# ShrewSpecs-1-2.net
KiCad netlist of a schematic drawn in EAGLE
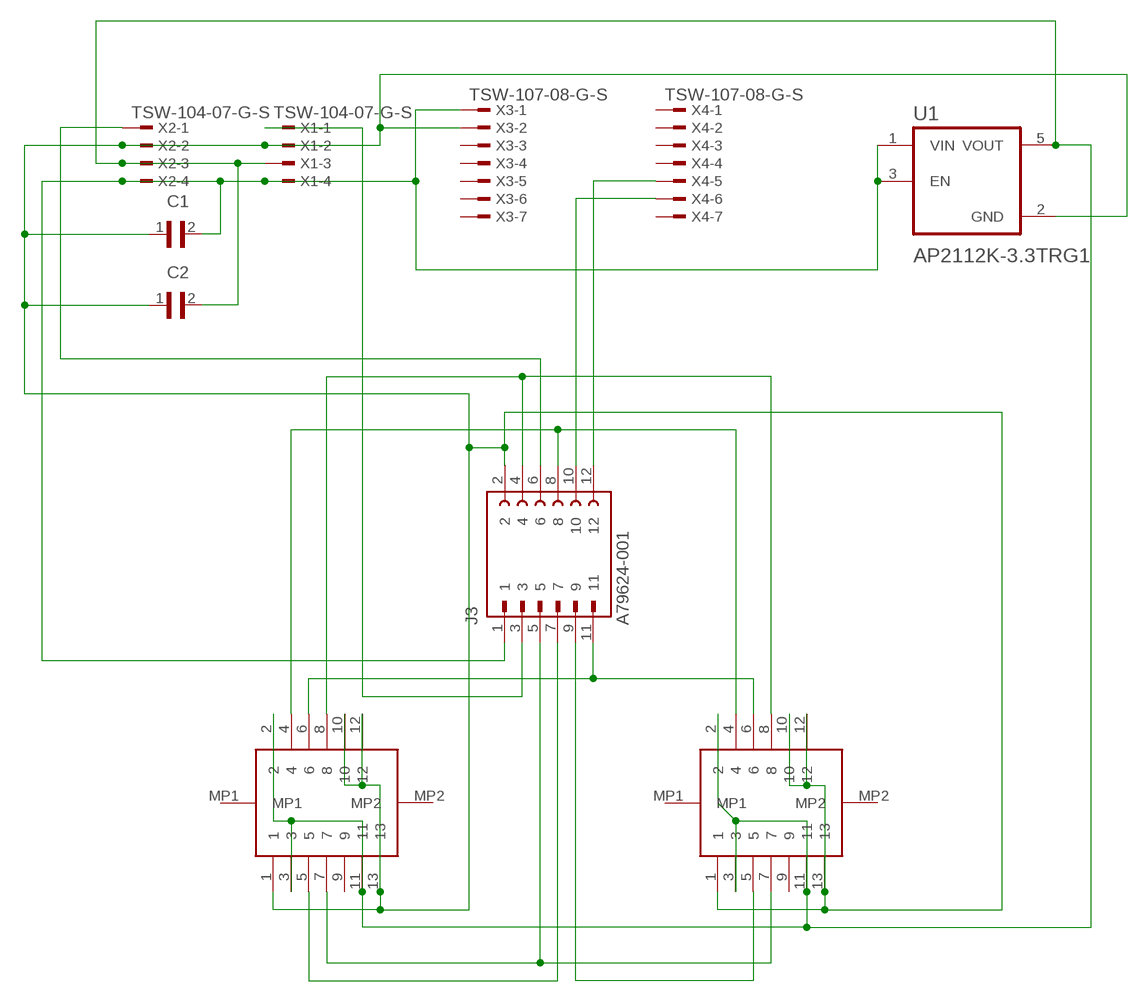
[diagram p0: schematic, sheet 1]

(export (version "E")
  (design (tool "Eeschema 10.0.6"))
  (components
    (comp (ref "C1")
      (value "CL21A106KOQNNNE")
      (footprint "eagle-import:CAPC2012X140N")
      (fields (field (name "MANUFACTURER") "Samsung Electro-Mechanics"))
      (libsource (lib "eagle-import") (part "CL21A106KOQNNNE"))
    )
    (comp (ref "C2")
      (value "CL21A106KOQNNNE")
      (footprint "eagle-import:CAPC2012X140N")
      (fields (field (name "MANUFACTURER") "Samsung Electro-Mechanics"))
      (libsource (lib "eagle-import") (part "CL21A106KOQNNNE"))
    )
    (comp (ref "J1")
      (value "1-2328724-3")
      (footprint "eagle-import:123287243")
      (fields (field (name "MOUSER_PART_NUMBER") "571-1-2328724-3"))
      (libsource (lib "eagle-import") (part "1-2328724-3"))
    )
    (comp (ref "J2")
      (value "1-2328724-3")
      (footprint "eagle-import:123287243")
      (fields (field (name "MOUSER_PART_NUMBER") "571-1-2328724-3"))
      (libsource (lib "eagle-import") (part "1-2328724-3"))
    )
    (comp (ref "J3")
      (value "A79624-001")
      (footprint "eagle-import:OMNETICS_A79624-001")
      (fields (field (name "MANUFACTURER") "Omnetics") (field (name "CREATOR") "DIZAR"))
      (libsource (lib "eagle-import") (part "A79624-001"))
    )
    (comp (ref "U1")
      (value "AP2112K-3.3TRG1")
      (footprint "eagle-import:SOT95P285X140-5N")
      (fields (field (name "MANUFACTURER") "Diodes Inc."))
      (libsource (lib "eagle-import") (part "AP2112K-3.3TRG1"))
    )
    (comp (ref "X1")
      (value "TSW-104-07-G-S")
      (footprint "eagle-import:TSW-104-XX-G-S")
      (fields (field (name "MF") "Samtec Inc."))
      (libsource (lib "eagle-import") (part "TSW-104--G-S07"))
    )
    (comp (ref "X2")
      (value "TSW-104-07-G-S")
      (footprint "eagle-import:TSW-104-XX-G-S")
      (fields (field (name "MF") "Samtec Inc."))
      (libsource (lib "eagle-import") (part "TSW-104--G-S07"))
    )
    (comp (ref "X3")
      (value "TSW-107-08-G-S")
      (footprint "eagle-import:TSW-107-XX-G-S")
      (fields (field (name "MF") "Samtec Inc.") (field (name "MPN") "TSW-107-07-G-S"))
      (libsource (lib "eagle-import") (part "TSW-107--G-S08"))
    )
    (comp (ref "X4")
      (value "TSW-107-08-G-S")
      (footprint "eagle-import:TSW-107-XX-G-S")
      (fields (field (name "MF") "Samtec Inc.") (field (name "MPN") "TSW-107-07-G-S"))
      (libsource (lib "eagle-import") (part "TSW-107--G-S08"))
    )
  )
  (nets
    (net (code "1") (name "Net-(J1-Pad4)") (class "Default")
      (node (ref "J1") (pin "4") (pinfunction "4_4") (pintype "bidirectional"))
      (node (ref "J2") (pin "4") (pinfunction "4_4") (pintype "bidirectional"))
      (node (ref "J3") (pin "8") (pinfunction "8_8") (pintype "passive"))
    )
    (net (code "2") (name "Net-(J1-Pad5)") (class "Default")
      (node (ref "J1") (pin "5") (pinfunction "5_5") (pintype "bidirectional"))
      (node (ref "J3") (pin "7") (pinfunction "7_7") (pintype "passive"))
    )
    (net (code "3") (name "Net-(J1-Pad6)") (class "Default")
      (node (ref "J1") (pin "6") (pinfunction "6_6") (pintype "bidirectional"))
      (node (ref "J2") (pin "6") (pinfunction "6_6") (pintype "bidirectional"))
      (node (ref "J3") (pin "11") (pinfunction "11_11") (pintype "passive"))
    )
    (net (code "4") (name "Net-(J1-Pad7)") (class "Default")
      (node (ref "J1") (pin "7") (pinfunction "7_7") (pintype "bidirectional"))
      (node (ref "J2") (pin "7") (pinfunction "7_7") (pintype "bidirectional"))
      (node (ref "J3") (pin "5") (pinfunction "5_5") (pintype "passive"))
    )
    (net (code "5") (name "Net-(J1-Pad8)") (class "Default")
      (node (ref "J1") (pin "8") (pinfunction "8_8") (pintype "bidirectional"))
      (node (ref "J2") (pin "8") (pinfunction "8_8") (pintype "bidirectional"))
      (node (ref "J3") (pin "4") (pinfunction "4_4") (pintype "passive"))
    )
    (net (code "6") (name "Net-(J2-Pad5)") (class "Default")
      (node (ref "J2") (pin "5") (pinfunction "5_5") (pintype "bidirectional"))
      (node (ref "J3") (pin "9") (pinfunction "9_9") (pintype "passive"))
    )
    (net (code "7") (name "Net-(J3-Pad3)") (class "Default")
      (node (ref "J3") (pin "3") (pinfunction "3_3") (pintype "passive"))
      (node (ref "X1") (pin "1") (pinfunction "1_1") (pintype "passive"))
    )
    (net (code "8") (name "Net-(J3-Pad6)") (class "Default")
      (node (ref "J3") (pin "6") (pinfunction "6_6") (pintype "passive"))
      (node (ref "X2") (pin "1") (pinfunction "1_1") (pintype "passive"))
    )
    (net (code "9") (name "Net-(U1-EN)") (class "Default")
      (node (ref "C1") (pin "2") (pinfunction "2_2") (pintype "passive"))
      (node (ref "J3") (pin "1") (pinfunction "1_1") (pintype "passive"))
      (node (ref "U1") (pin "1") (pinfunction "VIN_1") (pintype "power_in"))
      (node (ref "U1") (pin "3") (pinfunction "EN_3") (pintype "input"))
      (node (ref "X1") (pin "4") (pinfunction "1_4") (pintype "passive"))
      (node (ref "X2") (pin "4") (pinfunction "1_4") (pintype "passive"))
      (node (ref "X3") (pin "1") (pinfunction "1_1") (pintype "passive"))
    )
    (net (code "10") (name "Net-(U1-GND)") (class "Default")
      (node (ref "C1") (pin "1") (pinfunction "1_1") (pintype "passive"))
      (node (ref "C2") (pin "1") (pinfunction "1_1") (pintype "passive"))
      (node (ref "J1") (pin "1") (pinfunction "1_1") (pintype "bidirectional"))
      (node (ref "J1") (pin "10") (pinfunction "10_10") (pintype "bidirectional"))
      (node (ref "J1") (pin "12") (pinfunction "12_12") (pintype "bidirectional"))
      (node (ref "J1") (pin "13") (pinfunction "13_13") (pintype "bidirectional"))
      (node (ref "J2") (pin "1") (pinfunction "1_1") (pintype "bidirectional"))
      (node (ref "J2") (pin "10") (pinfunction "10_10") (pintype "bidirectional"))
      (node (ref "J2") (pin "12") (pinfunction "12_12") (pintype "bidirectional"))
      (node (ref "J2") (pin "13") (pinfunction "13_13") (pintype "bidirectional"))
      (node (ref "J3") (pin "2") (pinfunction "2_2") (pintype "passive"))
      (node (ref "U1") (pin "2") (pinfunction "GND_2") (pintype "power_in"))
      (node (ref "X1") (pin "2") (pinfunction "1_2") (pintype "passive"))
      (node (ref "X2") (pin "2") (pinfunction "1_2") (pintype "passive"))
      (node (ref "X3") (pin "2") (pinfunction "1_2") (pintype "passive"))
    )
    (net (code "11") (name "Net-(U1-VOUT)") (class "Default")
      (node (ref "C2") (pin "2") (pinfunction "2_2") (pintype "passive"))
      (node (ref "J1") (pin "11") (pinfunction "11_11") (pintype "bidirectional"))
      (node (ref "J1") (pin "2") (pinfunction "2_2") (pintype "bidirectional"))
      (node (ref "J1") (pin "3") (pinfunction "3_3") (pintype "bidirectional"))
      (node (ref "J2") (pin "11") (pinfunction "11_11") (pintype "bidirectional"))
      (node (ref "J2") (pin "2") (pinfunction "2_2") (pintype "bidirectional"))
      (node (ref "J2") (pin "3") (pinfunction "3_3") (pintype "bidirectional"))
      (node (ref "U1") (pin "5") (pinfunction "VOUT_5") (pintype "power_in"))
      (node (ref "X1") (pin "3") (pinfunction "1_3") (pintype "passive"))
      (node (ref "X2") (pin "3") (pinfunction "1_3") (pintype "passive"))
    )
    (net (code "12") (name "Net-(X4E-1)") (class "Default")
      (node (ref "J3") (pin "12") (pinfunction "12_12") (pintype "passive"))
      (node (ref "X4") (pin "5") (pinfunction "1_5") (pintype "passive"))
    )
    (net (code "13") (name "Net-(X4F-1)") (class "Default")
      (node (ref "J3") (pin "10") (pinfunction "10_10") (pintype "passive"))
      (node (ref "X4") (pin "6") (pinfunction "1_6") (pintype "passive"))
    )
    (net (code "14") (name "unconnected-(J1-Pad9)") (class "Default")
      (node (ref "J1") (pin "9") (pinfunction "9_9") (pintype "bidirectional"))
    )
    (net (code "15") (name "unconnected-(J1-PadMP1)") (class "Default")
      (node (ref "J1") (pin "MP1") (pinfunction "MP1_MP1") (pintype "bidirectional"))
    )
    (net (code "16") (name "unconnected-(J1-PadMP2)") (class "Default")
      (node (ref "J1") (pin "MP2") (pinfunction "MP2_MP2") (pintype "bidirectional"))
    )
    (net (code "17") (name "unconnected-(J2-Pad9)") (class "Default")
      (node (ref "J2") (pin "9") (pinfunction "9_9") (pintype "bidirectional"))
    )
    (net (code "18") (name "unconnected-(J2-PadMP1)") (class "Default")
      (node (ref "J2") (pin "MP1") (pinfunction "MP1_MP1") (pintype "bidirectional"))
    )
    (net (code "19") (name "unconnected-(J2-PadMP2)") (class "Default")
      (node (ref "J2") (pin "MP2") (pinfunction "MP2_MP2") (pintype "bidirectional"))
    )
    (net (code "20") (name "unconnected-(X3C-1-Pad3)") (class "Default")
      (node (ref "X3") (pin "3") (pinfunction "1_3") (pintype "passive"))
    )
    (net (code "21") (name "unconnected-(X3D-1-Pad4)") (class "Default")
      (node (ref "X3") (pin "4") (pinfunction "1_4") (pintype "passive"))
    )
    (net (code "22") (name "unconnected-(X3E-1-Pad5)") (class "Default")
      (node (ref "X3") (pin "5") (pinfunction "1_5") (pintype "passive"))
    )
    (net (code "23") (name "unconnected-(X3F-1-Pad6)") (class "Default")
      (node (ref "X3") (pin "6") (pinfunction "1_6") (pintype "passive"))
    )
    (net (code "24") (name "unconnected-(X3G-1-Pad7)") (class "Default")
      (node (ref "X3") (pin "7") (pinfunction "1_7") (pintype "passive"))
    )
    (net (code "25") (name "unconnected-(X4-Pad1)") (class "Default")
      (node (ref "X4") (pin "1") (pinfunction "1_1") (pintype "passive"))
    )
    (net (code "26") (name "unconnected-(X4B-1-Pad2)") (class "Default")
      (node (ref "X4") (pin "2") (pinfunction "1_2") (pintype "passive"))
    )
    (net (code "27") (name "unconnected-(X4C-1-Pad3)") (class "Default")
      (node (ref "X4") (pin "3") (pinfunction "1_3") (pintype "passive"))
    )
    (net (code "28") (name "unconnected-(X4D-1-Pad4)") (class "Default")
      (node (ref "X4") (pin "4") (pinfunction "1_4") (pintype "passive"))
    )
    (net (code "29") (name "unconnected-(X4G-1-Pad7)") (class "Default")
      (node (ref "X4") (pin "7") (pinfunction "1_7") (pintype "passive"))
    )
  )
)
